# dual_encoder_shield_5v_reva.net
KiCad netlist of a schematic drawn in EAGLE
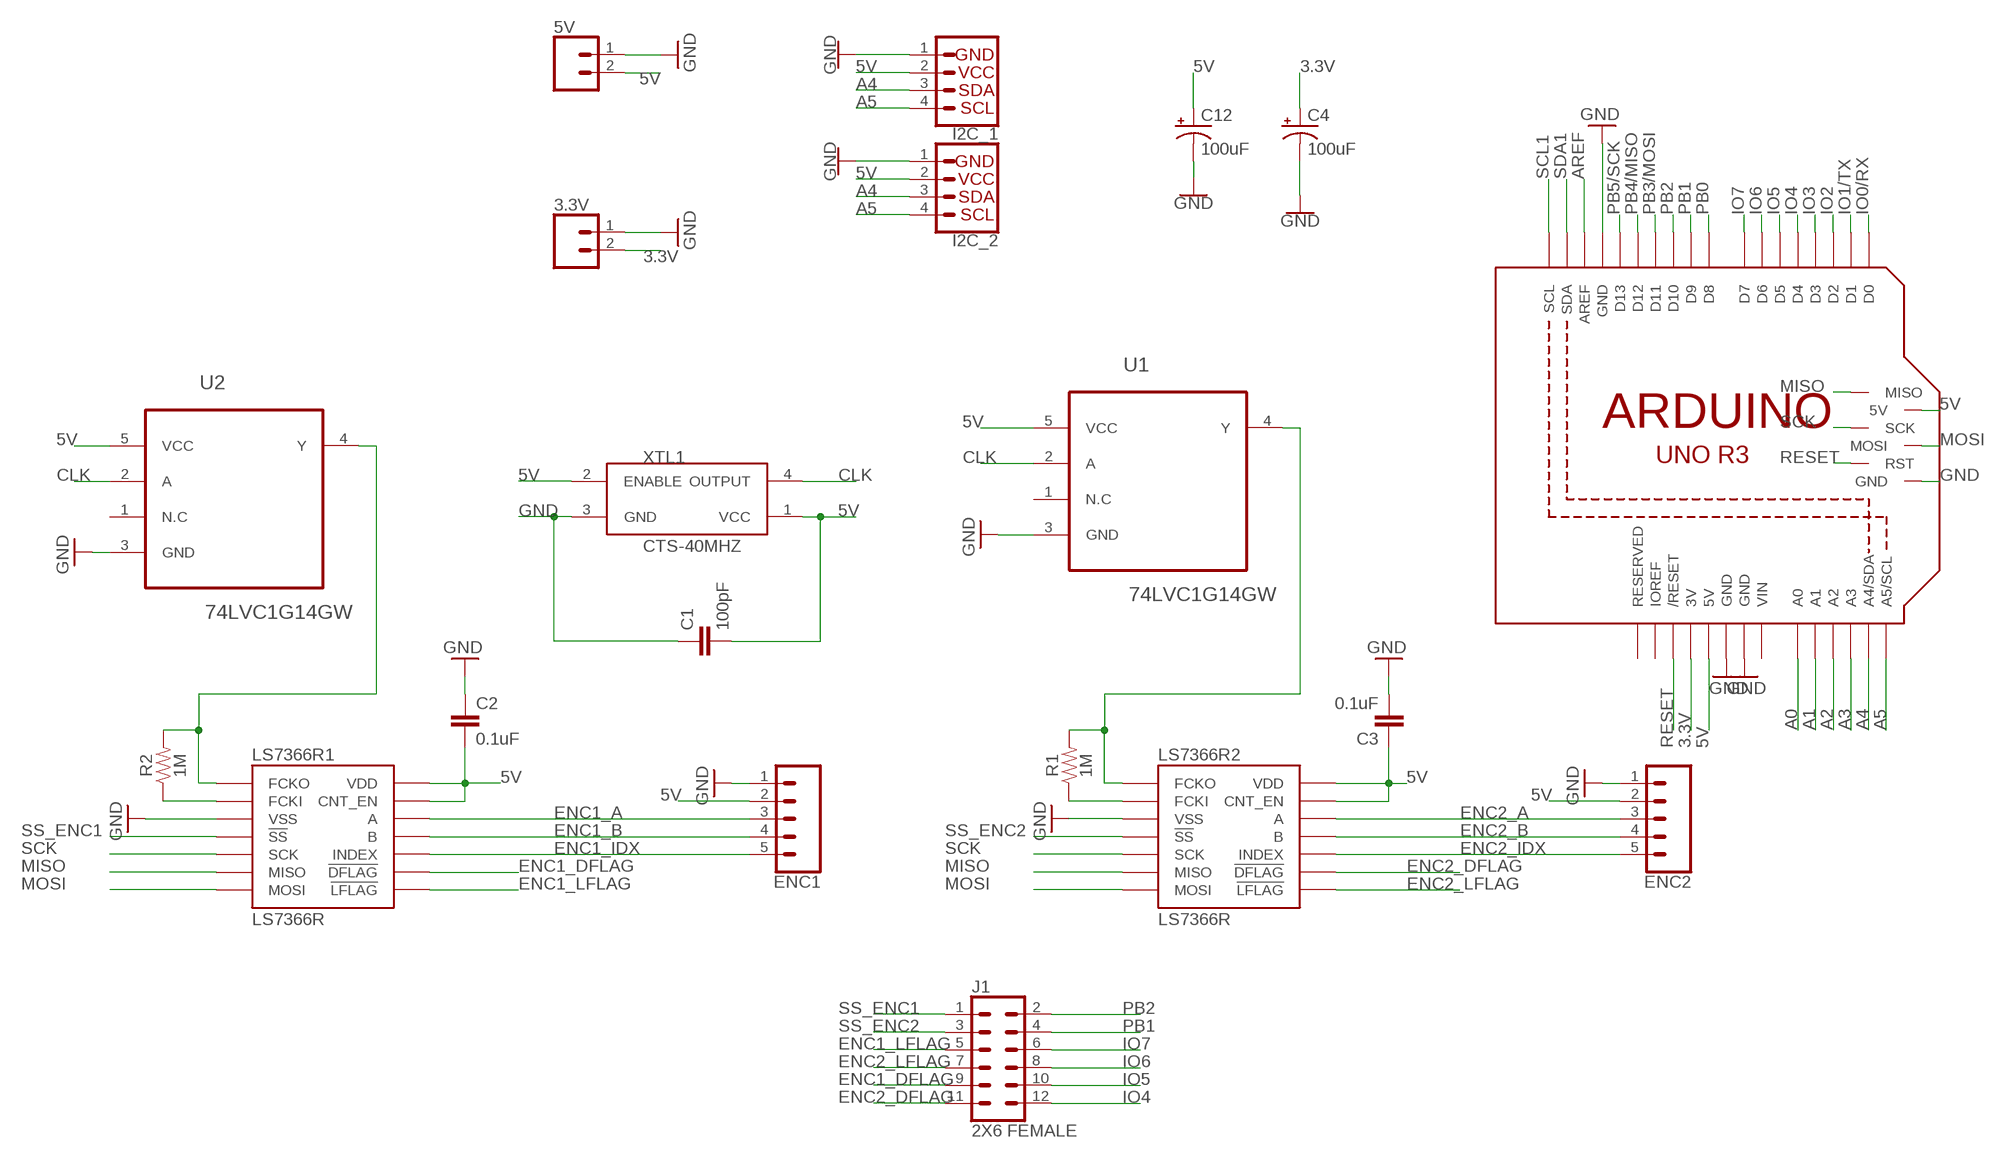
[diagram p0: schematic, sheet 1]

(export (version "E")
  (design (tool "Eeschema 10.0.6"))
  (components
    (comp (ref "3.3V")
      (value "CONN_02-JST-2MM-SMT")
      (footprint "eagle-import:JST-2-SMD")
      (libsource (lib "eagle-import") (part "CONN_02-JST-2MM-SMT"))
    )
    (comp (ref "5V")
      (value "CONN_02-JST-2MM-SMT")
      (footprint "eagle-import:JST-2-SMD")
      (libsource (lib "eagle-import") (part "CONN_02-JST-2MM-SMT"))
    )
    (comp (ref "C1")
      (value "100pF")
      (footprint "eagle-import:0603")
      (libsource (lib "eagle-import") (part "100PF-0603-50V-5%"))
    )
    (comp (ref "C2")
      (value "0.1uF")
      (footprint "eagle-import:0603")
      (libsource (lib "eagle-import") (part "0.1UF-0603-25V-5%"))
    )
    (comp (ref "C3")
      (value "0.1uF")
      (footprint "eagle-import:0603")
      (libsource (lib "eagle-import") (part "0.1UF-0603-25V-5%"))
    )
    (comp (ref "C4")
      (value "100uF")
      (footprint "eagle-import:PANASONIC_D")
      (libsource (lib "eagle-import") (part "100UF-POLAR-25V-20%(ELEC)"))
    )
    (comp (ref "C12")
      (value "100uF")
      (footprint "eagle-import:PANASONIC_D")
      (libsource (lib "eagle-import") (part "100UF-POLAR-25V-20%(ELEC)"))
    )
    (comp (ref "ENC1")
      (value "CONN_05")
      (footprint "eagle-import:1X05")
      (libsource (lib "eagle-import") (part "CONN_05"))
    )
    (comp (ref "ENC2")
      (value "CONN_05")
      (footprint "eagle-import:1X05")
      (libsource (lib "eagle-import") (part "CONN_05"))
    )
    (comp (ref "I2C_1")
      (value "QWIIC_CONNECTORJS-1MM")
      (footprint "eagle-import:JST04_1MM_RA")
      (libsource (lib "eagle-import") (part "QWIIC_CONNECTORJS-1MM"))
    )
    (comp (ref "I2C_2")
      (value "QWIIC_CONNECTORJS-1MM")
      (footprint "eagle-import:JST04_1MM_RA")
      (libsource (lib "eagle-import") (part "QWIIC_CONNECTORJS-1MM"))
    )
    (comp (ref "J1")
      (value "2X6 FEMALE")
      (footprint "eagle-import:2X6")
      (libsource (lib "eagle-import") (part "CONN_06X2PTH_FEMALE"))
    )
    (comp (ref "LS7366R1")
      (value "LS7366R")
      (footprint "eagle-import:SOIC14")
      (fields (field (name "MF") "LSI"))
      (libsource (lib "eagle-import") (part "LS7366R"))
    )
    (comp (ref "LS7366R2")
      (value "LS7366R")
      (footprint "eagle-import:SOIC14")
      (fields (field (name "MF") "LSI"))
      (libsource (lib "eagle-import") (part "LS7366R"))
    )
    (comp (ref "M1")
      (value "ARDUINO_R3_ICSP")
      (footprint "eagle-import:ARDUINOR3_ICSP")
      (libsource (lib "eagle-import") (part "ARDUINO_R3_ICSP"))
    )
    (comp (ref "R1")
      (value "1M")
      (footprint "eagle-import:0603")
      (libsource (lib "eagle-import") (part "1MOHM-0603-1/4W-5%"))
    )
    (comp (ref "R2")
      (value "1M")
      (footprint "eagle-import:0603")
      (libsource (lib "eagle-import") (part "1MOHM-0603-1/4W-5%"))
    )
    (comp (ref "U1")
      (value "74LVC1G14GW")
      (footprint "eagle-import:SOT65P210X110-5N")
      (fields (field (name "MF") "NXP Semiconductors"))
      (libsource (lib "eagle-import") (part "74LVC1G14GW"))
    )
    (comp (ref "U2")
      (value "74LVC1G14GW")
      (footprint "eagle-import:SOT65P210X110-5N")
      (fields (field (name "MF") "NXP Semiconductors"))
      (libsource (lib "eagle-import") (part "74LVC1G14GW"))
    )
    (comp (ref "XTL1")
      (value "CTS-40MHZ")
      (footprint "eagle-import:SOIC254P1016X440-4N")
      (libsource (lib "eagle-import") (part "CTS-40MHZ"))
    )
  )
  (nets
    (net (code "1") (name "/3.3V") (class "Default")
      (node (ref "3.3V") (pin "2") (pinfunction "1_2") (pintype "passive"))
      (node (ref "C4") (pin "+") (pinfunction "+_+") (pintype "passive"))
      (node (ref "M1") (pin "3V") (pinfunction "3V_3V") (pintype "power_in"))
    )
    (net (code "2") (name "/5V") (class "Default")
      (node (ref "5V") (pin "2") (pinfunction "1_2") (pintype "passive"))
      (node (ref "C1") (pin "2") (pinfunction "2_2") (pintype "passive"))
      (node (ref "C12") (pin "+") (pinfunction "+_+") (pintype "passive"))
      (node (ref "C2") (pin "2") (pinfunction "2_2") (pintype "passive"))
      (node (ref "C3") (pin "1") (pinfunction "1_1") (pintype "passive"))
      (node (ref "ENC1") (pin "2") (pinfunction "2_2") (pintype "passive"))
      (node (ref "ENC2") (pin "2") (pinfunction "2_2") (pintype "passive"))
      (node (ref "I2C_1") (pin "2") (pinfunction "2_2") (pintype "power_in"))
      (node (ref "I2C_2") (pin "2") (pinfunction "2_2") (pintype "power_in"))
      (node (ref "LS7366R1") (pin "13") (pinfunction "CNT_EN_13") (pintype "bidirectional"))
      (node (ref "LS7366R1") (pin "14") (pinfunction "VDD_14") (pintype "bidirectional"))
      (node (ref "LS7366R2") (pin "13") (pinfunction "CNT_EN_13") (pintype "bidirectional"))
      (node (ref "LS7366R2") (pin "14") (pinfunction "VDD_14") (pintype "bidirectional"))
      (node (ref "M1") (pin "5V") (pinfunction "5V_5V") (pintype "power_in"))
      (node (ref "M1") (pin "5V_ICSP") (pinfunction "5V_5V_ICSP") (pintype "passive"))
      (node (ref "U1") (pin "5") (pinfunction "VCC_5") (pintype "power_in"))
      (node (ref "U2") (pin "5") (pinfunction "VCC_5") (pintype "power_in"))
      (node (ref "XTL1") (pin "1") (pinfunction "VCC_1") (pintype "bidirectional"))
      (node (ref "XTL1") (pin "2") (pinfunction "ENABLE_2") (pintype "bidirectional"))
    )
    (net (code "3") (name "/A0") (class "Default")
      (node (ref "M1") (pin "A0") (pinfunction "A0_A0") (pintype "bidirectional"))
    )
    (net (code "4") (name "/A1") (class "Default")
      (node (ref "M1") (pin "A1") (pinfunction "A1_A1") (pintype "bidirectional"))
    )
    (net (code "5") (name "/A2") (class "Default")
      (node (ref "M1") (pin "A2") (pinfunction "A2_A2") (pintype "bidirectional"))
    )
    (net (code "6") (name "/A3") (class "Default")
      (node (ref "M1") (pin "A3") (pinfunction "A3_A3") (pintype "bidirectional"))
    )
    (net (code "7") (name "/A4") (class "Default")
      (node (ref "I2C_1") (pin "3") (pinfunction "3_3") (pintype "passive"))
      (node (ref "I2C_2") (pin "3") (pinfunction "3_3") (pintype "passive"))
      (node (ref "M1") (pin "A4") (pinfunction "A4/SDA_A4") (pintype "bidirectional"))
    )
    (net (code "8") (name "/A5") (class "Default")
      (node (ref "I2C_1") (pin "4") (pinfunction "4_4") (pintype "passive"))
      (node (ref "I2C_2") (pin "4") (pinfunction "4_4") (pintype "passive"))
      (node (ref "M1") (pin "A5") (pinfunction "A5/SCL_A5") (pintype "bidirectional"))
    )
    (net (code "9") (name "/AREF") (class "Default")
      (node (ref "M1") (pin "AREF") (pinfunction "AREF_AREF") (pintype "bidirectional"))
    )
    (net (code "10") (name "/CLK") (class "Default")
      (node (ref "U1") (pin "2") (pinfunction "A_2") (pintype "input"))
      (node (ref "U2") (pin "2") (pinfunction "A_2") (pintype "input"))
      (node (ref "XTL1") (pin "4") (pinfunction "OUTPUT_4") (pintype "bidirectional"))
    )
    (net (code "11") (name "/ENC1_A") (class "Default")
      (node (ref "ENC1") (pin "3") (pinfunction "3_3") (pintype "passive"))
      (node (ref "LS7366R1") (pin "12") (pinfunction "A_12") (pintype "bidirectional"))
    )
    (net (code "12") (name "/ENC1_B") (class "Default")
      (node (ref "ENC1") (pin "4") (pinfunction "4_4") (pintype "passive"))
      (node (ref "LS7366R1") (pin "11") (pinfunction "B_11") (pintype "bidirectional"))
    )
    (net (code "13") (name "/ENC1_DFLAG") (class "Default")
      (node (ref "J1") (pin "9") (pinfunction "9_9") (pintype "passive"))
      (node (ref "LS7366R1") (pin "9") (pinfunction "~{DFLAG}_9") (pintype "bidirectional"))
    )
    (net (code "14") (name "/ENC1_IDX") (class "Default")
      (node (ref "ENC1") (pin "5") (pinfunction "5_5") (pintype "passive"))
      (node (ref "LS7366R1") (pin "10") (pinfunction "INDEX_10") (pintype "bidirectional"))
    )
    (net (code "15") (name "/ENC1_LFLAG") (class "Default")
      (node (ref "J1") (pin "5") (pinfunction "5_5") (pintype "passive"))
      (node (ref "LS7366R1") (pin "8") (pinfunction "~{LFLAG}_8") (pintype "bidirectional"))
    )
    (net (code "16") (name "/ENC2_A") (class "Default")
      (node (ref "ENC2") (pin "3") (pinfunction "3_3") (pintype "passive"))
      (node (ref "LS7366R2") (pin "12") (pinfunction "A_12") (pintype "bidirectional"))
    )
    (net (code "17") (name "/ENC2_B") (class "Default")
      (node (ref "ENC2") (pin "4") (pinfunction "4_4") (pintype "passive"))
      (node (ref "LS7366R2") (pin "11") (pinfunction "B_11") (pintype "bidirectional"))
    )
    (net (code "18") (name "/ENC2_DFLAG") (class "Default")
      (node (ref "J1") (pin "11") (pinfunction "11_11") (pintype "passive"))
      (node (ref "LS7366R2") (pin "9") (pinfunction "~{DFLAG}_9") (pintype "bidirectional"))
    )
    (net (code "19") (name "/ENC2_IDX") (class "Default")
      (node (ref "ENC2") (pin "5") (pinfunction "5_5") (pintype "passive"))
      (node (ref "LS7366R2") (pin "10") (pinfunction "INDEX_10") (pintype "bidirectional"))
    )
    (net (code "20") (name "/ENC2_LFLAG") (class "Default")
      (node (ref "J1") (pin "7") (pinfunction "7_7") (pintype "passive"))
      (node (ref "LS7366R2") (pin "8") (pinfunction "~{LFLAG}_8") (pintype "bidirectional"))
    )
    (net (code "21") (name "/IO0{slash}RX") (class "Default")
      (node (ref "M1") (pin "D0") (pinfunction "D0_D0") (pintype "bidirectional"))
    )
    (net (code "22") (name "/IO1{slash}TX") (class "Default")
      (node (ref "M1") (pin "D1") (pinfunction "D1_D1") (pintype "bidirectional"))
    )
    (net (code "23") (name "/IO2") (class "Default")
      (node (ref "M1") (pin "D2") (pinfunction "D2_D2") (pintype "bidirectional"))
    )
    (net (code "24") (name "/IO3") (class "Default")
      (node (ref "M1") (pin "D3") (pinfunction "D3_D3") (pintype "bidirectional"))
    )
    (net (code "25") (name "/IO4") (class "Default")
      (node (ref "J1") (pin "12") (pinfunction "12_12") (pintype "passive"))
      (node (ref "M1") (pin "D4") (pinfunction "D4_D4") (pintype "bidirectional"))
    )
    (net (code "26") (name "/IO5") (class "Default")
      (node (ref "J1") (pin "10") (pinfunction "10_10") (pintype "passive"))
      (node (ref "M1") (pin "D5") (pinfunction "D5_D5") (pintype "bidirectional"))
    )
    (net (code "27") (name "/IO6") (class "Default")
      (node (ref "J1") (pin "8") (pinfunction "8_8") (pintype "passive"))
      (node (ref "M1") (pin "D6") (pinfunction "D6_D6") (pintype "bidirectional"))
    )
    (net (code "28") (name "/IO7") (class "Default")
      (node (ref "J1") (pin "6") (pinfunction "6_6") (pintype "passive"))
      (node (ref "M1") (pin "D7") (pinfunction "D7_D7") (pintype "bidirectional"))
    )
    (net (code "29") (name "/MISO") (class "Default")
      (node (ref "LS7366R1") (pin "6") (pinfunction "MISO_6") (pintype "bidirectional"))
      (node (ref "LS7366R2") (pin "6") (pinfunction "MISO_6") (pintype "bidirectional"))
      (node (ref "M1") (pin "MISO") (pinfunction "MISO_MISO") (pintype "passive"))
    )
    (net (code "30") (name "/MOSI") (class "Default")
      (node (ref "LS7366R1") (pin "7") (pinfunction "MOSI_7") (pintype "bidirectional"))
      (node (ref "LS7366R2") (pin "7") (pinfunction "MOSI_7") (pintype "bidirectional"))
      (node (ref "M1") (pin "MOSI") (pinfunction "MOSI_MOSI") (pintype "passive"))
    )
    (net (code "31") (name "/PB0") (class "Default")
      (node (ref "M1") (pin "D8") (pinfunction "D8_D8") (pintype "bidirectional"))
    )
    (net (code "32") (name "/PB1") (class "Default")
      (node (ref "J1") (pin "4") (pinfunction "4_4") (pintype "passive"))
      (node (ref "M1") (pin "D9") (pinfunction "D9_D9") (pintype "bidirectional"))
    )
    (net (code "33") (name "/PB2") (class "Default")
      (node (ref "J1") (pin "2") (pinfunction "2_2") (pintype "passive"))
      (node (ref "M1") (pin "D10") (pinfunction "D10_D10") (pintype "bidirectional"))
    )
    (net (code "34") (name "/PB3{slash}MOSI") (class "Default")
      (node (ref "M1") (pin "D11") (pinfunction "D11_D11") (pintype "bidirectional"))
    )
    (net (code "35") (name "/PB4{slash}MISO") (class "Default")
      (node (ref "M1") (pin "D12") (pinfunction "D12_D12") (pintype "bidirectional"))
    )
    (net (code "36") (name "/PB5{slash}SCK") (class "Default")
      (node (ref "M1") (pin "D13") (pinfunction "D13_D13") (pintype "bidirectional"))
    )
    (net (code "37") (name "/RESET") (class "Default")
      (node (ref "M1") (pin "RESET") (pinfunction "/RESET_RESET") (pintype "bidirectional"))
      (node (ref "M1") (pin "RESET_ICSP") (pinfunction "RST_RESET_ICSP") (pintype "passive"))
    )
    (net (code "38") (name "/SCK") (class "Default")
      (node (ref "LS7366R1") (pin "5") (pinfunction "SCK_5") (pintype "bidirectional"))
      (node (ref "LS7366R2") (pin "5") (pinfunction "SCK_5") (pintype "bidirectional"))
      (node (ref "M1") (pin "SCK") (pinfunction "SCK_SCK") (pintype "passive"))
    )
    (net (code "39") (name "/SCL1") (class "Default")
      (node (ref "M1") (pin "SCL") (pinfunction "SCL_SCL") (pintype "bidirectional"))
    )
    (net (code "40") (name "/SDA1") (class "Default")
      (node (ref "M1") (pin "SDA") (pinfunction "SDA_SDA") (pintype "bidirectional"))
    )
    (net (code "41") (name "/SS_ENC1") (class "Default")
      (node (ref "J1") (pin "1") (pinfunction "1_1") (pintype "passive"))
      (node (ref "LS7366R1") (pin "4") (pinfunction "~{SS}_4") (pintype "bidirectional"))
    )
    (net (code "42") (name "/SS_ENC2") (class "Default")
      (node (ref "J1") (pin "3") (pinfunction "3_3") (pintype "passive"))
      (node (ref "LS7366R2") (pin "4") (pinfunction "~{SS}_4") (pintype "bidirectional"))
    )
    (net (code "43") (name "/VIN") (class "Default")
      (node (ref "M1") (pin "VIN") (pinfunction "VIN_VIN") (pintype "power_in"))
    )
    (net (code "44") (name "GND") (class "Default")
      (node (ref "3.3V") (pin "1") (pinfunction "2_1") (pintype "passive"))
      (node (ref "5V") (pin "1") (pinfunction "2_1") (pintype "passive"))
      (node (ref "C1") (pin "1") (pinfunction "1_1") (pintype "passive"))
      (node (ref "C12") (pin "-") (pinfunction "-_-") (pintype "passive"))
      (node (ref "C2") (pin "1") (pinfunction "1_1") (pintype "passive"))
      (node (ref "C3") (pin "2") (pinfunction "2_2") (pintype "passive"))
      (node (ref "C4") (pin "-") (pinfunction "-_-") (pintype "passive"))
      (node (ref "ENC1") (pin "1") (pinfunction "1_1") (pintype "passive"))
      (node (ref "ENC2") (pin "1") (pinfunction "1_1") (pintype "passive"))
      (node (ref "I2C_1") (pin "1") (pinfunction "1_1") (pintype "power_in"))
      (node (ref "I2C_2") (pin "1") (pinfunction "1_1") (pintype "power_in"))
      (node (ref "LS7366R1") (pin "3") (pinfunction "VSS_3") (pintype "bidirectional"))
      (node (ref "LS7366R2") (pin "3") (pinfunction "VSS_3") (pintype "bidirectional"))
      (node (ref "M1") (pin "GND") (pinfunction "GND_GND") (pintype "power_in"))
      (node (ref "M1") (pin "GND@1") (pinfunction "GND_GND@1") (pintype "power_in"))
      (node (ref "M1") (pin "GND@2") (pinfunction "GND_GND@2") (pintype "passive"))
      (node (ref "M1") (pin "GND@3") (pinfunction "GND_GND@3") (pintype "power_in"))
      (node (ref "U1") (pin "3") (pinfunction "GND_3") (pintype "passive"))
      (node (ref "U2") (pin "3") (pinfunction "GND_3") (pintype "passive"))
      (node (ref "XTL1") (pin "3") (pinfunction "GND_3") (pintype "bidirectional"))
    )
    (net (code "45") (name "Net-(LS7366R1-FCKI)") (class "Default")
      (node (ref "LS7366R1") (pin "2") (pinfunction "FCKI_2") (pintype "bidirectional"))
      (node (ref "R2") (pin "1") (pinfunction "1_1") (pintype "passive"))
    )
    (net (code "46") (name "Net-(LS7366R1-FCKO)") (class "Default")
      (node (ref "LS7366R1") (pin "1") (pinfunction "FCKO_1") (pintype "bidirectional"))
      (node (ref "R2") (pin "2") (pinfunction "2_2") (pintype "passive"))
      (node (ref "U2") (pin "4") (pinfunction "Y_4") (pintype "output"))
    )
    (net (code "47") (name "Net-(LS7366R2-FCKI)") (class "Default")
      (node (ref "LS7366R2") (pin "2") (pinfunction "FCKI_2") (pintype "bidirectional"))
      (node (ref "R1") (pin "1") (pinfunction "1_1") (pintype "passive"))
    )
    (net (code "48") (name "Net-(LS7366R2-FCKO)") (class "Default")
      (node (ref "LS7366R2") (pin "1") (pinfunction "FCKO_1") (pintype "bidirectional"))
      (node (ref "R1") (pin "2") (pinfunction "2_2") (pintype "passive"))
      (node (ref "U1") (pin "4") (pinfunction "Y_4") (pintype "output"))
    )
    (net (code "49") (name "unconnected-(M1-PadIOREF)") (class "Default")
      (node (ref "M1") (pin "IOREF") (pinfunction "IOREF_IOREF") (pintype "output"))
    )
    (net (code "50") (name "unconnected-(M1-PadRESERVED)") (class "Default")
      (node (ref "M1") (pin "RESERVED") (pinfunction "RESERVED_RESERVED") (pintype "no_connect"))
    )
    (net (code "51") (name "unconnected-(U1-N.C-Pad1)") (class "Default")
      (node (ref "U1") (pin "1") (pinfunction "N.C_1") (pintype "no_connect"))
    )
    (net (code "52") (name "unconnected-(U2-N.C-Pad1)") (class "Default")
      (node (ref "U2") (pin "1") (pinfunction "N.C_1") (pintype "no_connect"))
    )
  )
)
